# sensors.net
KiCad netlist of a schematic drawn in Altium Designer
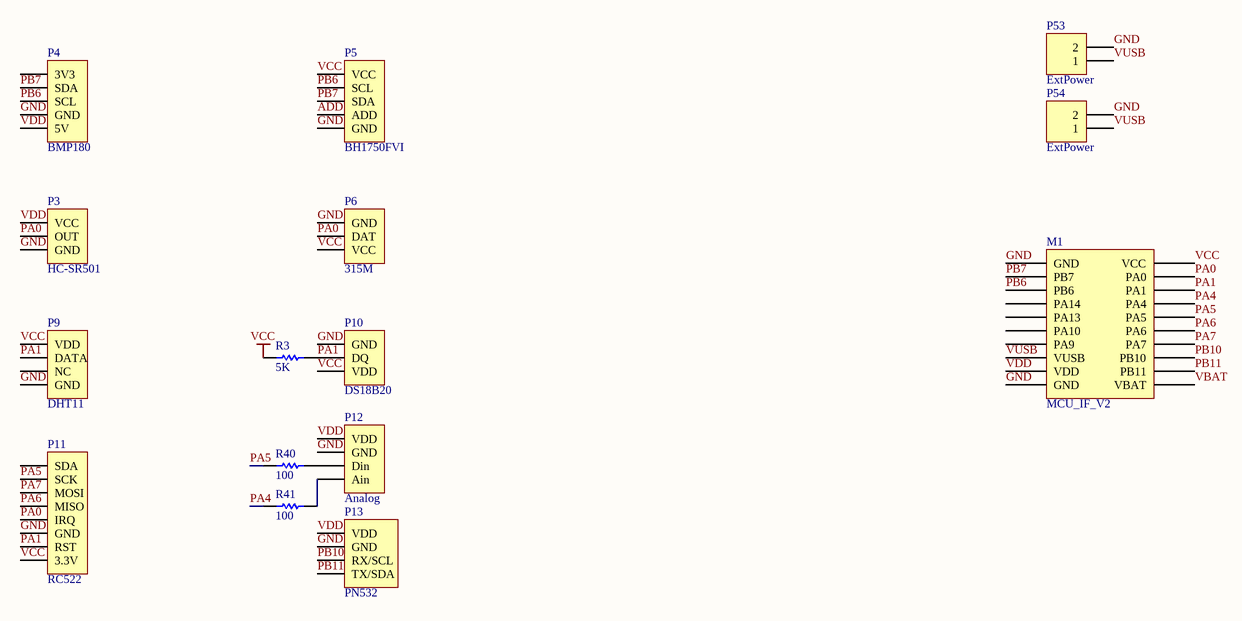
[diagram p0: sensors.SchDoc]

(export (version "E")
  (design (tool "Eeschema 10.0.6"))
  (components
    (comp (ref "M1")
      (value "MCU_IF_V2")
      (footprint "MCU_IF_V2")
      (libsource (lib "MCU_IF") (part "MCU_IF_V1"))
    )
    (comp (ref "P3")
      (value "HC-SR501")
      (footprint "HDR1X3")
      (description "Header, 3-Pin")
      (fields (field (name "PUBLISHER") "Altium Limited"))
      (libsource (lib "sensor_ifce") (part "HC-SR501"))
    )
    (comp (ref "P4")
      (value "BMP180")
      (footprint "HDR1X5")
      (description "Header, 5-Pin")
      (fields (field (name "PUBLISHER") "Altium Limited"))
      (libsource (lib "sensor_ifce") (part "BMP180"))
    )
    (comp (ref "P5")
      (value "BH1750FVI")
      (footprint "HDR1X5")
      (fields (field (name "PUBLISHER") "Altium Limited"))
      (libsource (lib "sensor_ifce") (part "BH1750FVI"))
    )
    (comp (ref "P6")
      (value "315M")
      (footprint "HDR1X3")
      (description "Header, 3-Pin")
      (fields (field (name "PUBLISHER") "Altium Limited"))
      (libsource (lib "sensor_ifce") (part "315M"))
    )
    (comp (ref "P9")
      (value "DHT11")
      (footprint "HDR1X4")
      (description "Header, 4-Pin")
      (fields (field (name "PUBLISHER") "Altium Limited"))
      (libsource (lib "sensor_ifce") (part "DHT11"))
    )
    (comp (ref "P10")
      (value "DS18B20")
      (footprint "HDR1X3")
      (description "Header, 3-Pin")
      (fields (field (name "PUBLISHER") "Altium Limited"))
      (libsource (lib "sensor_ifce") (part "DS18B20"))
    )
    (comp (ref "P11")
      (value "RC522")
      (footprint "HDR1X8")
      (description "Header, 8-Pin")
      (fields (field (name "PUBLISHER") "Altium Limited"))
      (libsource (lib "sensor_ifce") (part "RC522"))
    )
    (comp (ref "P12")
      (value "Analog")
      (footprint "HDR1X4")
      (description "Header, 4-Pin")
      (fields (field (name "PUBLISHER") "Altium Limited"))
      (libsource (lib "sensor_ifce") (part "Analog"))
    )
    (comp (ref "P13")
      (value "PN532")
      (footprint "HDR1X4")
      (description "Header, 4-Pin")
      (fields (field (name "PUBLISHER") "Altium Limited"))
      (libsource (lib "sensor_ifce") (part "PN532"))
    )
    (comp (ref "P53")
      (value "ExtPower")
      (footprint "HDR1X2H")
      (description "Header, 2-Pin, Right Angle")
      (fields (field (name "PUBLISHER") "Altium Limited"))
      (libsource (lib "Miscellaneous Connectors") (part "Header 2H"))
    )
    (comp (ref "P54")
      (value "ExtPower")
      (footprint "HDR1X2H")
      (description "Header, 2-Pin, Right Angle")
      (fields (field (name "PUBLISHER") "Altium Limited"))
      (libsource (lib "Miscellaneous Connectors") (part "Header 2H"))
    )
    (comp (ref "R3")
      (value "5K")
      (footprint "R-1608[0603]")
      (description "Semiconductor Resistor")
      (fields (field (name "Comment") "Res Semi") (field (name "PUBLISHER") "Altium Limited"))
      (libsource (lib "Miscellaneous Devices") (part "Res Semi"))
    )
    (comp (ref "R40")
      (value "100")
      (footprint "R-1608[0603]")
      (description "Semiconductor Resistor")
      (fields (field (name "Comment") "Res Semi") (field (name "PUBLISHER") "Altium Limited"))
      (libsource (lib "Miscellaneous Devices") (part "Res Semi"))
    )
    (comp (ref "R41")
      (value "100")
      (footprint "R-1608[0603]")
      (description "Semiconductor Resistor")
      (fields (field (name "Comment") "Res Semi") (field (name "PUBLISHER") "Altium Limited"))
      (libsource (lib "Miscellaneous Devices") (part "Res Semi"))
    )
  )
  (nets
    (net (code "1") (name "/ADD") (class "Default")
      (node (ref "P5") (pin "4") (pinfunction "ADD_4") (pintype "passive"))
    )
    (net (code "2") (name "/GND") (class "Default")
      (node (ref "M1") (pin "1") (pinfunction "GND_1") (pintype "passive"))
      (node (ref "M1") (pin "10") (pinfunction "GND_10") (pintype "passive"))
      (node (ref "P10") (pin "1") (pinfunction "GND_1") (pintype "passive"))
      (node (ref "P11") (pin "6") (pinfunction "GND_6") (pintype "passive"))
      (node (ref "P12") (pin "2") (pinfunction "GND_2") (pintype "passive"))
      (node (ref "P13") (pin "2") (pinfunction "GND_2") (pintype "passive"))
      (node (ref "P3") (pin "3") (pinfunction "GND_3") (pintype "passive"))
      (node (ref "P4") (pin "4") (pinfunction "GND_4") (pintype "passive"))
      (node (ref "P5") (pin "5") (pinfunction "GND_5") (pintype "passive"))
      (node (ref "P53") (pin "2") (pinfunction "2_2") (pintype "passive"))
      (node (ref "P54") (pin "2") (pinfunction "2_2") (pintype "passive"))
      (node (ref "P6") (pin "1") (pinfunction "GND_1") (pintype "passive"))
      (node (ref "P9") (pin "4") (pinfunction "GND_4") (pintype "passive"))
    )
    (net (code "3") (name "/PA0") (class "Default")
      (node (ref "M1") (pin "19") (pinfunction "PA0_19") (pintype "passive"))
      (node (ref "P11") (pin "5") (pinfunction "IRQ_5") (pintype "passive"))
      (node (ref "P3") (pin "2") (pinfunction "OUT_2") (pintype "passive"))
      (node (ref "P6") (pin "2") (pinfunction "DAT_2") (pintype "passive"))
    )
    (net (code "4") (name "/PA1") (class "Default")
      (node (ref "M1") (pin "18") (pinfunction "PA1_18") (pintype "passive"))
      (node (ref "P10") (pin "2") (pinfunction "DQ_2") (pintype "passive"))
      (node (ref "P11") (pin "7") (pinfunction "RST_7") (pintype "passive"))
      (node (ref "P9") (pin "2") (pinfunction "DATA_2") (pintype "passive"))
      (node (ref "R3") (pin "2") (pinfunction "2_2") (pintype "passive"))
    )
    (net (code "5") (name "/PA4") (class "Default")
      (node (ref "M1") (pin "17") (pinfunction "PA4_17") (pintype "passive"))
      (node (ref "R41") (pin "1") (pinfunction "1_1") (pintype "passive"))
    )
    (net (code "6") (name "/PA5") (class "Default")
      (node (ref "M1") (pin "16") (pinfunction "PA5_16") (pintype "passive"))
      (node (ref "P11") (pin "2") (pinfunction "SCK_2") (pintype "passive"))
      (node (ref "R40") (pin "1") (pinfunction "1_1") (pintype "passive"))
    )
    (net (code "7") (name "/PA6") (class "Default")
      (node (ref "M1") (pin "15") (pinfunction "PA6_15") (pintype "passive"))
      (node (ref "P11") (pin "4") (pinfunction "MISO_4") (pintype "passive"))
    )
    (net (code "8") (name "/PA7") (class "Default")
      (node (ref "M1") (pin "14") (pinfunction "PA7_14") (pintype "passive"))
      (node (ref "P11") (pin "3") (pinfunction "MOSI_3") (pintype "passive"))
    )
    (net (code "9") (name "/PB6") (class "Default")
      (node (ref "M1") (pin "3") (pinfunction "PB6_3") (pintype "passive"))
      (node (ref "P4") (pin "3") (pinfunction "SCL_3") (pintype "passive"))
      (node (ref "P5") (pin "2") (pinfunction "SCL_2") (pintype "passive"))
    )
    (net (code "10") (name "/PB7") (class "Default")
      (node (ref "M1") (pin "2") (pinfunction "PB7_2") (pintype "passive"))
      (node (ref "P4") (pin "2") (pinfunction "SDA_2") (pintype "passive"))
      (node (ref "P5") (pin "3") (pinfunction "SDA_3") (pintype "passive"))
    )
    (net (code "11") (name "/PB10") (class "Default")
      (node (ref "M1") (pin "13") (pinfunction "PB10_13") (pintype "passive"))
      (node (ref "P13") (pin "3") (pinfunction "RX/SCL_3") (pintype "passive"))
    )
    (net (code "12") (name "/PB11") (class "Default")
      (node (ref "M1") (pin "12") (pinfunction "PB11_12") (pintype "passive"))
      (node (ref "P13") (pin "4") (pinfunction "TX/SDA_4") (pintype "passive"))
    )
    (net (code "13") (name "/VBAT") (class "Default")
      (node (ref "M1") (pin "11") (pinfunction "VBAT_11") (pintype "passive"))
    )
    (net (code "14") (name "/VDD") (class "Default")
      (node (ref "M1") (pin "9") (pinfunction "VDD_9") (pintype "passive"))
      (node (ref "P12") (pin "1") (pinfunction "VDD_1") (pintype "passive"))
      (node (ref "P13") (pin "1") (pinfunction "VDD_1") (pintype "passive"))
      (node (ref "P3") (pin "1") (pinfunction "VCC_1") (pintype "passive"))
      (node (ref "P4") (pin "5") (pinfunction "5V_5") (pintype "passive"))
    )
    (net (code "15") (name "/VUSB") (class "Default")
      (node (ref "M1") (pin "8") (pinfunction "VUSB_8") (pintype "passive"))
      (node (ref "P53") (pin "1") (pinfunction "1_1") (pintype "passive"))
      (node (ref "P54") (pin "1") (pinfunction "1_1") (pintype "passive"))
    )
    (net (code "16") (name "Net-(P12-Ain)") (class "Default")
      (node (ref "P12") (pin "4") (pinfunction "Ain_4") (pintype "passive"))
      (node (ref "R41") (pin "2") (pinfunction "2_2") (pintype "passive"))
    )
    (net (code "17") (name "Net-(P12-Din)") (class "Default")
      (node (ref "P12") (pin "3") (pinfunction "Din_3") (pintype "passive"))
      (node (ref "R40") (pin "2") (pinfunction "2_2") (pintype "passive"))
    )
    (net (code "18") (name "VCC") (class "Default")
      (node (ref "M1") (pin "20") (pinfunction "VCC_20") (pintype "passive"))
      (node (ref "P10") (pin "3") (pinfunction "VDD_3") (pintype "passive"))
      (node (ref "P11") (pin "8") (pinfunction "3.3V_8") (pintype "passive"))
      (node (ref "P5") (pin "1") (pinfunction "VCC_1") (pintype "passive"))
      (node (ref "P6") (pin "3") (pinfunction "VCC_3") (pintype "passive"))
      (node (ref "P9") (pin "1") (pinfunction "VDD_1") (pintype "passive"))
      (node (ref "R3") (pin "1") (pinfunction "1_1") (pintype "passive"))
    )
    (net (code "19") (name "unconnected-(M1-PA9-Pad7)") (class "Default")
      (node (ref "M1") (pin "7") (pinfunction "PA9_7") (pintype "passive"))
    )
    (net (code "20") (name "unconnected-(M1-PA10-Pad6)") (class "Default")
      (node (ref "M1") (pin "6") (pinfunction "PA10_6") (pintype "passive"))
    )
    (net (code "21") (name "unconnected-(M1-PA13-Pad5)") (class "Default")
      (node (ref "M1") (pin "5") (pinfunction "PA13_5") (pintype "passive"))
    )
    (net (code "22") (name "unconnected-(M1-PA14-Pad4)") (class "Default")
      (node (ref "M1") (pin "4") (pinfunction "PA14_4") (pintype "passive"))
    )
    (net (code "23") (name "unconnected-(P4-3V3-Pad1)") (class "Default")
      (node (ref "P4") (pin "1") (pinfunction "3V3_1") (pintype "passive"))
    )
    (net (code "24") (name "unconnected-(P9-NC-Pad3)") (class "Default")
      (node (ref "P9") (pin "3") (pinfunction "NC_3") (pintype "passive"))
    )
    (net (code "25") (name "unconnected-(P11-SDA-Pad1)") (class "Default")
      (node (ref "P11") (pin "1") (pinfunction "SDA_1") (pintype "passive"))
    )
  )
)
